# ESP32S3.net
KiCad netlist of a schematic drawn in Altium Designer
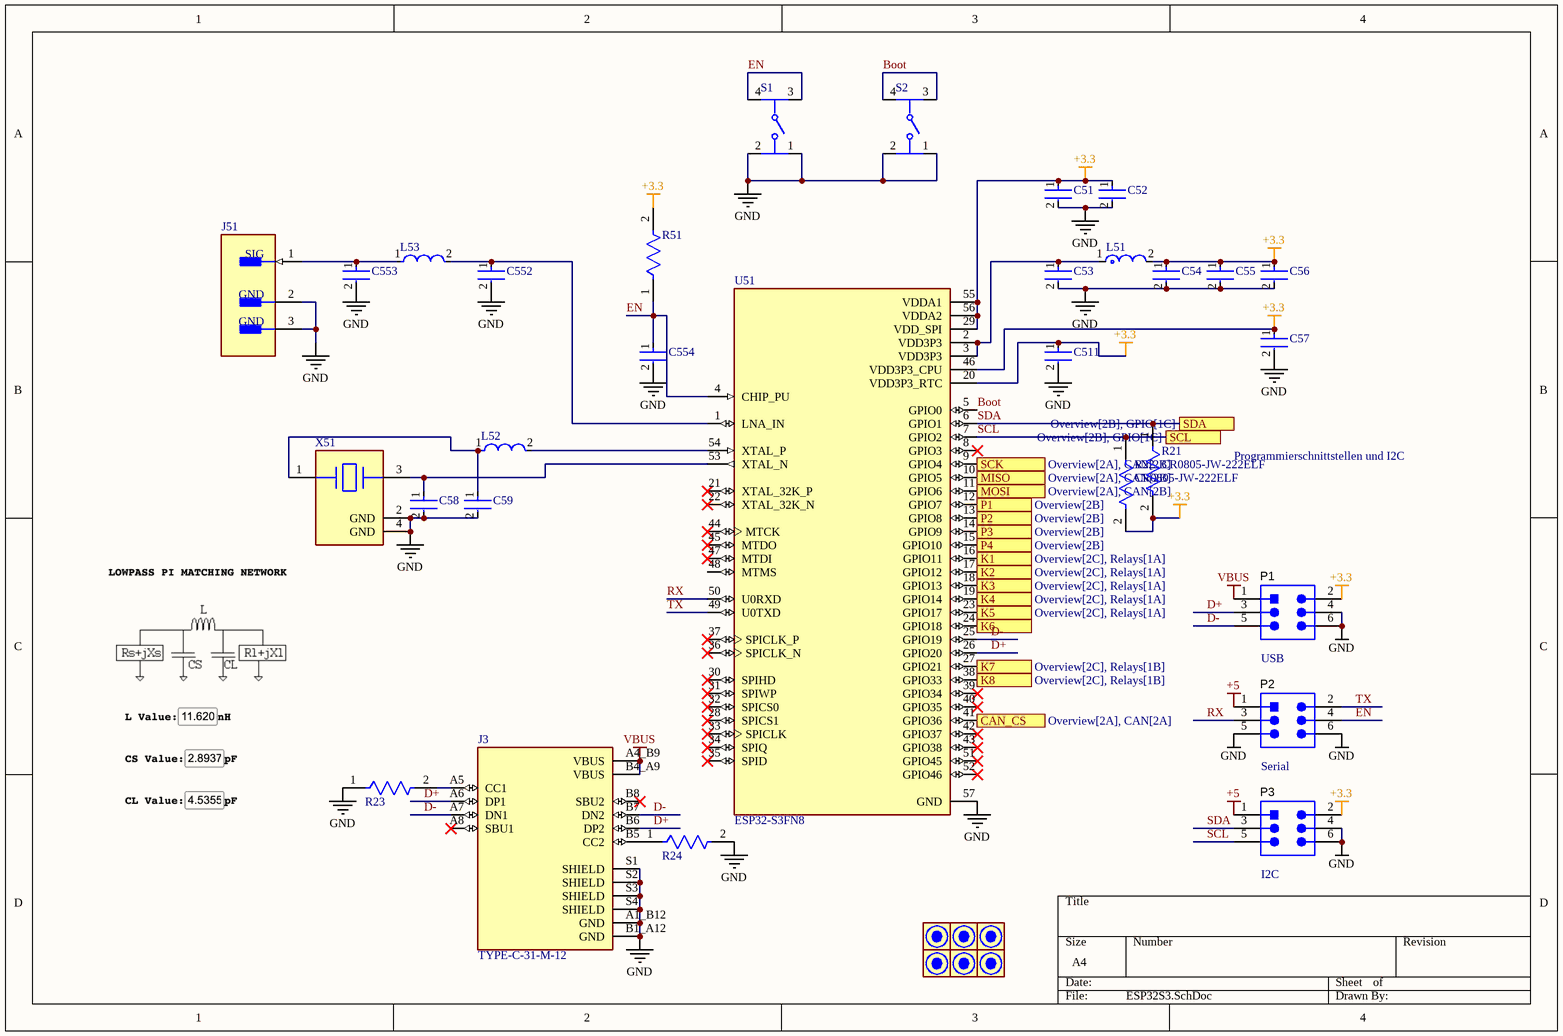
[diagram p0: ESP32S3.SchDoc]

(export (version "E")
  (design (tool "Eeschema 10.0.6"))
  (components
    (comp (ref "C51")
      (value "GRM155R61A105KE15D")
      (footprint "FP-GRM15-0_1-MFG")
      (description "CAP CER 1UF 10V X5R 0402")
      (fields
        (field (name "OCTOPART") "https://octopart.com/grm155r61a105ke15d-murata-197442")
        (field (name "MANUFACTURER") "Murata")
      )
      (libsource (lib "Altium Content Vault") (part "02cd4be3c70576c341d710602a673aa"))
    )
    (comp (ref "C52")
      (value "C0603C103K8RACTU")
      (footprint "FP-C0603C-CF-MFG")
      (description "CAP CER 10000PF 10V X7R 0603")
      (fields
        (field (name "OCTOPART") "https://octopart.com/c0603c103k8ractu-kemet-8375724")
        (field (name "MANUFACTURER") "KEMET")
      )
      (libsource (lib "Altium Content Vault") (part "b4654b650e69147ec39a6b967a45e02"))
    )
    (comp (ref "C53")
      (value "CC0402KRX7R6BB104")
      (footprint "FP-CC0402-MFG")
      (description "CAP CER 0.1UF 10V X7R 0402")
      (fields (field (name "MANUFACTURER") "YAGEO") (field (name "TOLERANCE") "0.1"))
      (libsource (lib "Altium Content Vault") (part "11868f565c42a9108669ba33697ecf6"))
    )
    (comp (ref "C54")
      (value "C0402C104K8PACTU")
      (footprint "FP-C0402-BB-MFG")
      (description "CAP CER 0.1UF 10V X5R 0402")
      (fields (field (name "MANUFACTURER") "Kemet") (field (name "TOLERANCE") "0.1"))
      (libsource (lib "Altium Content Vault") (part "b4654b650e69147ec39a6b967a45e02"))
    )
    (comp (ref "C55")
      (value "GRM155R61A105KE15D")
      (footprint "FP-GRM15-0_1-MFG")
      (description "CAP CER 1UF 10V X5R 0402")
      (fields
        (field (name "OCTOPART") "https://octopart.com/grm155r61a105ke15d-murata-197442")
        (field (name "MANUFACTURER") "Murata")
      )
      (libsource (lib "Altium Content Vault") (part "02cd4be3c70576c341d710602a673aa"))
    )
    (comp (ref "C56")
      (value "CL05A106MP5NUNC")
      (footprint "FP-CL05A106MP5NUNC-MFG")
      (description "CAP CER 10UF 10V X5R 0402")
      (fields
        (field (name "OCTOPART") "https://octopart.com/cl05a106mp5nunc-samsung-22457395")
        (field (name "TOLERANCE") "20%")
      )
      (libsource (lib "Altium Content Vault") (part "b4654b650e69147ec39a6b967a45e02"))
    )
    (comp (ref "C57")
      (value "C0402C104K8PACTU")
      (footprint "FP-C0402-BB-MFG")
      (description "CAP CER 0.1UF 10V X5R 0402")
      (fields (field (name "MANUFACTURER") "Kemet") (field (name "TOLERANCE") "0.1"))
      (libsource (lib "Altium Content Vault") (part "b4654b650e69147ec39a6b967a45e02"))
    )
    (comp (ref "C58")
      (value "C0603C160J5GACTU")
      (footprint "FP-C0603C-CF-MFG")
      (description "CAP CER 16PF 50V 5% NP0 0603")
      (fields
        (field (name "OCTOPART") "https://octopart.com/c0603c160j5gactu-kemet-9143816")
        (field (name "MANUFACTURER") "KEMET")
      )
      (libsource (lib "Altium Content Vault") (part "b4654b650e69147ec39a6b967a45e02"))
    )
    (comp (ref "C59")
      (value "C0603C160J5GACTU")
      (footprint "FP-C0603C-CF-MFG")
      (description "CAP CER 16PF 50V 5% NP0 0603")
      (fields
        (field (name "OCTOPART") "https://octopart.com/c0603c160j5gactu-kemet-9143816")
        (field (name "MANUFACTURER") "KEMET")
      )
      (libsource (lib "Altium Content Vault") (part "b4654b650e69147ec39a6b967a45e02"))
    )
    (comp (ref "C511")
      (value "CC0402KRX7R6BB104")
      (footprint "FP-CC0402-MFG")
      (description "CAP CER 0.1UF 10V X7R 0402")
      (fields (field (name "MANUFACTURER") "YAGEO") (field (name "TOLERANCE") "0.1"))
      (libsource (lib "Altium Content Vault") (part "11868f565c42a9108669ba33697ecf6"))
    )
    (comp (ref "C552")
      (value "GJM1555C1H2R8WB01D")
      (footprint "FP-GJM155-0_05-IPC_C")
      (description "Multi-Layer Ceramic Capacitor 2.8pF C0G  ±0.05pF 0402 Paper T/R")
      (libsource (lib "Altium Content Vault") (part "02cd4be3c70576c341d710602a673aa"))
    )
    (comp (ref "C553")
      (value "GJM1555C1H4R5BB01D")
      (footprint "FP-GJM155-0_05-IPC_C")
      (description "Multi-Layer Ceramic Capacitor 4.5pF C0G  ±0.1pF 0402 Paper T/R")
      (libsource (lib "Altium Content Vault") (part "02cd4be3c70576c341d710602a673aa"))
    )
    (comp (ref "C554")
      (value "C0402C123K4RACTU")
      (footprint "FP-C0402-BB-MFG")
      (description "CAP CER 0.012UF 16V X7R 0402")
      (fields (field (name "TOLERANCE") "0.1") (field (name "MANUFACTURER") "Kemet"))
      (libsource (lib "Altium Content Vault") (part "b4654b650e69147ec39a6b967a45e02"))
    )
    (comp (ref "J3")
      (value "TYPE-C-31-M-12")
      (footprint "HRO_TYPE-C-31-M-12")
      (description "USB Connectors 24 Receptacle 1 8.94*7.3mm RoHS")
      (fields (field (name "MF") "HRO Electronics Co., Ltd."))
      (libsource (lib "Milutin") (part "TYPE-C-31-M-12"))
    )
    (comp (ref "J51")
      (value "U.FL-R-SMT-1(10)")
      (footprint "FP-U_FL-R-SMT-1_10-MFG")
      (description "CONN U.FL RCPT STR 50 OHM SMD")
      (libsource (lib "Altium Content Vault") (part "7158abf7d987fa84906f6fb0d115710"))
    )
    (comp (ref "L51")
      (value "LQP03TN2N0B02D")
      (footprint "FP-LQP03TG_02-IPC_A")
      (description "Film type RF Inductor 2nH ±0.1nH 600mA 0.15Ω 0201 (0603)")
      (libsource (lib "Altium Content Vault") (part "4cc4b267dca4c8e51f7102f422741d8"))
    )
    (comp (ref "L52")
      (value "LQW15AN20NG00D")
      (footprint "FP-LQW15AN_00-W0_6-0_1-MFG")
      (description "Wire Wound RF Inductor 20nH ±2% 370mA 0.27Ω 0402 (1005)")
      (fields (field (name "TOLERANCE") "2%"))
      (libsource (lib "Altium Content Vault") (part "725321dda6339637d4d059423bc1c3c"))
    )
    (comp (ref "L53")
      (value "LQW15AN11NG00D")
      (footprint "FP-LQW15AN_00-W0_6-0_1-MFG")
      (description "Wire Wound RF Inductor 11nH ±2% 500mA 0.14Ω 0402 (1005)")
      (fields (field (name "TOLERANCE") "2%"))
      (libsource (lib "Altium Content Vault") (part "725321dda6339637d4d059423bc1c3c"))
    )
    (comp (ref "P1")
      (value "5-146130-2")
      (footprint "TECO-5-146130-2_V")
      (description "Male Header, Pitch 2.54 mm, 2 x 3 Position, Height 8.13 mm, -65 to 125 degC, RoHS, Tube")
      (libsource (lib "Altium Content Vault") (part "CN-2P-M-R6"))
    )
    (comp (ref "P2")
      (value "5-146130-2")
      (footprint "TECO-5-146130-2_V")
      (description "Male Header, Pitch 2.54 mm, 2 x 3 Position, Height 8.13 mm, -65 to 125 degC, RoHS, Tube")
      (libsource (lib "Altium Content Vault") (part "CN-2P-M-R6"))
    )
    (comp (ref "P3")
      (value "5-146130-2")
      (footprint "TECO-5-146130-2_V")
      (description "Male Header, Pitch 2.54 mm, 2 x 3 Position, Height 8.13 mm, -65 to 125 degC, RoHS, Tube")
      (libsource (lib "Altium Content Vault") (part "CN-2P-M-R6"))
    )
    (comp (ref "R21")
      (value "CR0805-JW-222ELF")
      (footprint "FP-CR0805-IPC_B")
      (description "Thick Film Chip Resistors 0805 2.2kΩ 0.125W 5% 200ppm/°C")
      (fields (field (name "TOLERANCE") "5%"))
      (libsource (lib "Altium Content Vault") (part "1029c3af85768c4190bb7ad29bc67b5"))
    )
    (comp (ref "R22")
      (value "CR0805-JW-222ELF")
      (footprint "FP-CR0805-IPC_B")
      (description "Thick Film Chip Resistors 0805 2.2kΩ 0.125W 5% 200ppm/°C")
      (fields (field (name "TOLERANCE") "5%"))
      (libsource (lib "Altium Content Vault") (part "1029c3af85768c4190bb7ad29bc67b5"))
    )
    (comp (ref "R23")
      (value "CRCW06035K10FKEA")
      (footprint "FP-CRCW0603-e3-IPC_C")
      (description "RES Thick Film, 5.1kΩ, 1%, 0.1W, 100ppm/°C, 0603")
      (fields (field (name "TOLERANCE") "1%"))
      (libsource (lib "Altium Content Vault") (part "1029c3af85768c4190bb7ad29bc67b5"))
    )
    (comp (ref "R24")
      (value "CRCW06035K10FKEA")
      (footprint "FP-CRCW0603-e3-IPC_C")
      (description "RES Thick Film, 5.1kΩ, 1%, 0.1W, 100ppm/°C, 0603")
      (fields (field (name "TOLERANCE") "1%"))
      (libsource (lib "Altium Content Vault") (part "1029c3af85768c4190bb7ad29bc67b5"))
    )
    (comp (ref "R51")
      (value "CRCW04021K00FKED")
      (footprint "FP-CRCW0402-e3-MFG")
      (description "RES Thick Film, 1kΩ, 1%, 0.063W, 100ppm/°C, 0402")
      (fields (field (name "TOLERANCE") "1%"))
      (libsource (lib "Altium Content Vault") (part "1029c3af85768c4190bb7ad29bc67b5"))
    )
    (comp (ref "S1")
      (value "~")
      (footprint "FP-PTS645SM43SMTR92LFS-MFG")
      (description "SWITCH TACTILE SPST-NO 0.05A 12V\r\nPTS645SM43SMTR92LFS")
      (libsource (lib "Altium Content Vault") (part "1adf0dd01260c80cf25a44bfd6b99ba"))
    )
    (comp (ref "S2")
      (value "~")
      (footprint "FP-PTS645SM43SMTR92LFS-MFG")
      (description "SWITCH TACTILE SPST-NO 0.05A 12V\r\nPTS645SM43SMTR92LFS")
      (libsource (lib "Altium Content Vault") (part "1adf0dd01260c80cf25a44bfd6b99ba"))
    )
    (comp (ref "U51")
      (value "ESP32-S3FN8")
      (footprint "QFN40P700X700X90-57N")
      (fields (field (name "MF") "Espressif Systems"))
      (libsource (lib "Schaltdose") (part "ESP32-S3FN8"))
    )
    (comp (ref "X51")
      (value "X252040MMB4SI")
      (footprint "FP-ABM10-MFG")
      (description "Crystal 40MHz ±20ppm 10pF SMD-4 2.5mm x 2mm")
      (fields (field (name "TOLERANCE") "20ppm"))
      (libsource (lib "Altium Content Vault") (part "0934ba461506c7e3a0bb4df7a4ed385"))
    )
  )
  (nets
    (net (code "1") (name "+3.3") (class "Default")
      (node (ref "C51") (pin "1") (pinfunction "1_1") (pintype "passive"))
      (node (ref "C511") (pin "1") (pinfunction "1_1") (pintype "passive"))
      (node (ref "C52") (pin "1") (pinfunction "1_1") (pintype "passive"))
      (node (ref "C54") (pin "1") (pinfunction "1_1") (pintype "passive"))
      (node (ref "C55") (pin "1") (pinfunction "1_1") (pintype "passive"))
      (node (ref "C56") (pin "1") (pinfunction "1_1") (pintype "passive"))
      (node (ref "C57") (pin "1") (pinfunction "1_1") (pintype "passive"))
      (node (ref "L51") (pin "2") (pinfunction "2_2") (pintype "passive"))
      (node (ref "P1") (pin "2") (pinfunction "2_2") (pintype "passive"))
      (node (ref "P3") (pin "2") (pinfunction "2_2") (pintype "passive"))
      (node (ref "R21") (pin "2") (pinfunction "2_2") (pintype "passive"))
      (node (ref "R22") (pin "2") (pinfunction "2_2") (pintype "passive"))
      (node (ref "R51") (pin "2") (pinfunction "2_2") (pintype "passive"))
      (node (ref "U51") (pin "20") (pinfunction "VDD3P3_RTC_20") (pintype "power_in"))
      (node (ref "U51") (pin "29") (pinfunction "VDD_SPI_29") (pintype "power_in"))
      (node (ref "U51") (pin "46") (pinfunction "VDD3P3_CPU_46") (pintype "power_in"))
      (node (ref "U51") (pin "55") (pinfunction "VDDA1_55") (pintype "power_in"))
      (node (ref "U51") (pin "56") (pinfunction "VDDA2_56") (pintype "power_in"))
    )
    (net (code "2") (name "+5") (class "Default")
      (node (ref "P2") (pin "1") (pinfunction "1_1") (pintype "passive"))
      (node (ref "P3") (pin "1") (pinfunction "1_1") (pintype "passive"))
    )
    (net (code "3") (name "/Boot") (class "Default")
      (node (ref "S2") (pin "3") (pinfunction "3_3") (pintype "passive"))
      (node (ref "S2") (pin "4") (pinfunction "4_4") (pintype "passive"))
      (node (ref "U51") (pin "5") (pinfunction "GPIO0_5") (pintype "bidirectional"))
    )
    (net (code "4") (name "/CAN_CS") (class "Default")
      (node (ref "U51") (pin "41") (pinfunction "GPIO36_41") (pintype "bidirectional"))
    )
    (net (code "5") (name "/D+") (class "Default")
      (node (ref "J3") (pin "A6") (pinfunction "DP1_A6") (pintype "bidirectional"))
      (node (ref "J3") (pin "B6") (pinfunction "DP2_B6") (pintype "bidirectional"))
      (node (ref "P1") (pin "3") (pinfunction "3_3") (pintype "passive"))
      (node (ref "U51") (pin "26") (pinfunction "GPIO20_26") (pintype "bidirectional"))
    )
    (net (code "6") (name "/D-") (class "Default")
      (node (ref "J3") (pin "A7") (pinfunction "DN1_A7") (pintype "bidirectional"))
      (node (ref "J3") (pin "B7") (pinfunction "DN2_B7") (pintype "bidirectional"))
      (node (ref "P1") (pin "5") (pinfunction "5_5") (pintype "passive"))
      (node (ref "U51") (pin "25") (pinfunction "GPIO19_25") (pintype "bidirectional"))
    )
    (net (code "7") (name "/EN") (class "Default")
      (node (ref "C554") (pin "1") (pinfunction "1_1") (pintype "passive"))
      (node (ref "P2") (pin "4") (pinfunction "4_4") (pintype "passive"))
      (node (ref "R51") (pin "1") (pinfunction "1_1") (pintype "passive"))
      (node (ref "S1") (pin "3") (pinfunction "3_3") (pintype "passive"))
      (node (ref "S1") (pin "4") (pinfunction "4_4") (pintype "passive"))
      (node (ref "U51") (pin "4") (pinfunction "CHIP_PU_4") (pintype "input"))
    )
    (net (code "8") (name "/K1") (class "Default")
      (node (ref "U51") (pin "16") (pinfunction "GPIO11_16") (pintype "bidirectional"))
    )
    (net (code "9") (name "/K2") (class "Default")
      (node (ref "U51") (pin "17") (pinfunction "GPIO12_17") (pintype "bidirectional"))
    )
    (net (code "10") (name "/K3") (class "Default")
      (node (ref "U51") (pin "18") (pinfunction "GPIO13_18") (pintype "bidirectional"))
    )
    (net (code "11") (name "/K4") (class "Default")
      (node (ref "U51") (pin "19") (pinfunction "GPIO14_19") (pintype "bidirectional"))
    )
    (net (code "12") (name "/K5") (class "Default")
      (node (ref "U51") (pin "23") (pinfunction "GPIO17_23") (pintype "bidirectional"))
    )
    (net (code "13") (name "/K6") (class "Default")
      (node (ref "U51") (pin "24") (pinfunction "GPIO18_24") (pintype "bidirectional"))
    )
    (net (code "14") (name "/K7") (class "Default")
      (node (ref "U51") (pin "27") (pinfunction "GPIO21_27") (pintype "bidirectional"))
    )
    (net (code "15") (name "/K8") (class "Default")
      (node (ref "U51") (pin "38") (pinfunction "GPIO33_38") (pintype "bidirectional"))
    )
    (net (code "16") (name "/MISO") (class "Default")
      (node (ref "U51") (pin "10") (pinfunction "GPIO5_10") (pintype "bidirectional"))
    )
    (net (code "17") (name "/MOSI") (class "Default")
      (node (ref "U51") (pin "11") (pinfunction "GPIO6_11") (pintype "bidirectional"))
    )
    (net (code "18") (name "/P1") (class "Default")
      (node (ref "U51") (pin "12") (pinfunction "GPIO7_12") (pintype "bidirectional"))
    )
    (net (code "19") (name "/P2") (class "Default")
      (node (ref "U51") (pin "13") (pinfunction "GPIO8_13") (pintype "bidirectional"))
    )
    (net (code "20") (name "/P3") (class "Default")
      (node (ref "U51") (pin "14") (pinfunction "GPIO9_14") (pintype "bidirectional"))
    )
    (net (code "21") (name "/P4") (class "Default")
      (node (ref "U51") (pin "15") (pinfunction "GPIO10_15") (pintype "bidirectional"))
    )
    (net (code "22") (name "/RX") (class "Default")
      (node (ref "P2") (pin "3") (pinfunction "3_3") (pintype "passive"))
      (node (ref "U51") (pin "50") (pinfunction "U0RXD_50") (pintype "bidirectional"))
    )
    (net (code "23") (name "/SCK") (class "Default")
      (node (ref "U51") (pin "9") (pinfunction "GPIO4_9") (pintype "bidirectional"))
    )
    (net (code "24") (name "/SCL") (class "Default")
      (node (ref "P3") (pin "5") (pinfunction "5_5") (pintype "passive"))
      (node (ref "R22") (pin "1") (pinfunction "1_1") (pintype "passive"))
      (node (ref "U51") (pin "7") (pinfunction "GPIO2_7") (pintype "bidirectional"))
    )
    (net (code "25") (name "/SDA") (class "Default")
      (node (ref "P3") (pin "3") (pinfunction "3_3") (pintype "passive"))
      (node (ref "R21") (pin "1") (pinfunction "1_1") (pintype "passive"))
      (node (ref "U51") (pin "6") (pinfunction "GPIO1_6") (pintype "bidirectional"))
    )
    (net (code "26") (name "/TX") (class "Default")
      (node (ref "P2") (pin "2") (pinfunction "2_2") (pintype "passive"))
      (node (ref "U51") (pin "49") (pinfunction "U0TXD_49") (pintype "bidirectional"))
    )
    (net (code "27") (name "GND") (class "Default")
      (node (ref "C51") (pin "2") (pinfunction "2_2") (pintype "passive"))
      (node (ref "C511") (pin "2") (pinfunction "2_2") (pintype "passive"))
      (node (ref "C52") (pin "2") (pinfunction "2_2") (pintype "passive"))
      (node (ref "C53") (pin "2") (pinfunction "2_2") (pintype "passive"))
      (node (ref "C54") (pin "2") (pinfunction "2_2") (pintype "passive"))
      (node (ref "C55") (pin "2") (pinfunction "2_2") (pintype "passive"))
      (node (ref "C552") (pin "2") (pinfunction "2_2") (pintype "passive"))
      (node (ref "C553") (pin "2") (pinfunction "2_2") (pintype "passive"))
      (node (ref "C554") (pin "2") (pinfunction "2_2") (pintype "passive"))
      (node (ref "C56") (pin "2") (pinfunction "2_2") (pintype "passive"))
      (node (ref "C57") (pin "2") (pinfunction "2_2") (pintype "passive"))
      (node (ref "C58") (pin "2") (pinfunction "2_2") (pintype "passive"))
      (node (ref "C59") (pin "2") (pinfunction "2_2") (pintype "passive"))
      (node (ref "J3") (pin "A1_B12") (pinfunction "GND_A1_B12") (pintype "power_in"))
      (node (ref "J3") (pin "B1_A12") (pinfunction "GND_B1_A12") (pintype "power_in"))
      (node (ref "J3") (pin "S1") (pinfunction "SHIELD_S1") (pintype "passive"))
      (node (ref "J3") (pin "S2") (pinfunction "SHIELD_S2") (pintype "passive"))
      (node (ref "J3") (pin "S3") (pinfunction "SHIELD_S3") (pintype "passive"))
      (node (ref "J3") (pin "S4") (pinfunction "SHIELD_S4") (pintype "passive"))
      (node (ref "J51") (pin "2") (pinfunction "GND_2") (pintype "power_in"))
      (node (ref "J51") (pin "3") (pinfunction "GND_3") (pintype "power_in"))
      (node (ref "P1") (pin "4") (pinfunction "4_4") (pintype "passive"))
      (node (ref "P1") (pin "6") (pinfunction "6_6") (pintype "passive"))
      (node (ref "P2") (pin "5") (pinfunction "5_5") (pintype "passive"))
      (node (ref "P2") (pin "6") (pinfunction "6_6") (pintype "passive"))
      (node (ref "P3") (pin "4") (pinfunction "4_4") (pintype "passive"))
      (node (ref "P3") (pin "6") (pinfunction "6_6") (pintype "passive"))
      (node (ref "R23") (pin "1") (pinfunction "1_1") (pintype "passive"))
      (node (ref "R24") (pin "2") (pinfunction "2_2") (pintype "passive"))
      (node (ref "S1") (pin "1") (pinfunction "1_1") (pintype "passive"))
      (node (ref "S1") (pin "2") (pinfunction "2_2") (pintype "passive"))
      (node (ref "S2") (pin "1") (pinfunction "1_1") (pintype "passive"))
      (node (ref "S2") (pin "2") (pinfunction "2_2") (pintype "passive"))
      (node (ref "U51") (pin "57") (pinfunction "GND_57") (pintype "power_in"))
      (node (ref "X51") (pin "2") (pinfunction "GND_2") (pintype "power_in"))
      (node (ref "X51") (pin "4") (pinfunction "GND_4") (pintype "power_in"))
    )
    (net (code "28") (name "Net-(C53-Pad1)") (class "Default")
      (node (ref "C53") (pin "1") (pinfunction "1_1") (pintype "passive"))
      (node (ref "L51") (pin "1") (pinfunction "1_1") (pintype "passive"))
      (node (ref "U51") (pin "2") (pinfunction "VDD3P3_2") (pintype "power_in"))
      (node (ref "U51") (pin "3") (pinfunction "VDD3P3_3") (pintype "power_in"))
    )
    (net (code "29") (name "Net-(C59-Pad1)") (class "Default")
      (node (ref "C59") (pin "1") (pinfunction "1_1") (pintype "passive"))
      (node (ref "L52") (pin "1") (pinfunction "1_1") (pintype "passive"))
      (node (ref "X51") (pin "1") (pinfunction "1_1") (pintype "passive"))
    )
    (net (code "30") (name "Net-(J3-CC1)") (class "Default")
      (node (ref "J3") (pin "A5") (pinfunction "CC1_A5") (pintype "bidirectional"))
      (node (ref "R23") (pin "2") (pinfunction "2_2") (pintype "passive"))
    )
    (net (code "31") (name "Net-(J3-CC2)") (class "Default")
      (node (ref "J3") (pin "B5") (pinfunction "CC2_B5") (pintype "bidirectional"))
      (node (ref "R24") (pin "1") (pinfunction "1_1") (pintype "passive"))
    )
    (net (code "32") (name "Net-(J51-SIG)") (class "Default")
      (node (ref "C553") (pin "1") (pinfunction "1_1") (pintype "passive"))
      (node (ref "J51") (pin "1") (pinfunction "SIG_1") (pintype "input"))
      (node (ref "L53") (pin "1") (pinfunction "1_1") (pintype "passive"))
    )
    (net (code "33") (name "Net-(U51-LNA_IN)") (class "Default")
      (node (ref "C552") (pin "1") (pinfunction "1_1") (pintype "passive"))
      (node (ref "L53") (pin "2") (pinfunction "2_2") (pintype "passive"))
      (node (ref "U51") (pin "1") (pinfunction "LNA_IN_1") (pintype "bidirectional"))
    )
    (net (code "34") (name "Net-(U51-XTAL_N)") (class "Default")
      (node (ref "C58") (pin "1") (pinfunction "1_1") (pintype "passive"))
      (node (ref "U51") (pin "53") (pinfunction "XTAL_N_53") (pintype "output"))
      (node (ref "X51") (pin "3") (pinfunction "3_3") (pintype "passive"))
    )
    (net (code "35") (name "Net-(U51-XTAL_P)") (class "Default")
      (node (ref "L52") (pin "2") (pinfunction "2_2") (pintype "passive"))
      (node (ref "U51") (pin "54") (pinfunction "XTAL_P_54") (pintype "input"))
    )
    (net (code "36") (name "VBUS") (class "Default")
      (node (ref "J3") (pin "A4_B9") (pinfunction "VBUS_A4_B9") (pintype "power_in"))
      (node (ref "J3") (pin "B4_A9") (pinfunction "VBUS_B4_A9") (pintype "power_in"))
      (node (ref "P1") (pin "1") (pinfunction "1_1") (pintype "passive"))
    )
    (net (code "37") (name "unconnected-(J3-SBU1-PadA8)") (class "Default")
      (node (ref "J3") (pin "A8") (pinfunction "SBU1_A8") (pintype "bidirectional+no_connect"))
    )
    (net (code "38") (name "unconnected-(J3-SBU2-PadB8)") (class "Default")
      (node (ref "J3") (pin "B8") (pinfunction "SBU2_B8") (pintype "bidirectional+no_connect"))
    )
    (net (code "39") (name "unconnected-(U51-GPIO3-Pad8)") (class "Default")
      (node (ref "U51") (pin "8") (pinfunction "GPIO3_8") (pintype "bidirectional+no_connect"))
    )
    (net (code "40") (name "unconnected-(U51-GPIO34-Pad39)") (class "Default")
      (node (ref "U51") (pin "39") (pinfunction "GPIO34_39") (pintype "bidirectional+no_connect"))
    )
    (net (code "41") (name "unconnected-(U51-GPIO35-Pad40)") (class "Default")
      (node (ref "U51") (pin "40") (pinfunction "GPIO35_40") (pintype "bidirectional+no_connect"))
    )
    (net (code "42") (name "unconnected-(U51-GPIO37-Pad42)") (class "Default")
      (node (ref "U51") (pin "42") (pinfunction "GPIO37_42") (pintype "bidirectional+no_connect"))
    )
    (net (code "43") (name "unconnected-(U51-GPIO38-Pad43)") (class "Default")
      (node (ref "U51") (pin "43") (pinfunction "GPIO38_43") (pintype "bidirectional+no_connect"))
    )
    (net (code "44") (name "unconnected-(U51-GPIO45-Pad51)") (class "Default")
      (node (ref "U51") (pin "51") (pinfunction "GPIO45_51") (pintype "bidirectional+no_connect"))
    )
    (net (code "45") (name "unconnected-(U51-GPIO46-Pad52)") (class "Default")
      (node (ref "U51") (pin "52") (pinfunction "GPIO46_52") (pintype "bidirectional+no_connect"))
    )
    (net (code "46") (name "unconnected-(U51-MTCK-Pad44)") (class "Default")
      (node (ref "U51") (pin "44") (pinfunction "MTCK_44") (pintype "bidirectional+no_connect"))
    )
    (net (code "47") (name "unconnected-(U51-MTDI-Pad47)") (class "Default")
      (node (ref "U51") (pin "47") (pinfunction "MTDI_47") (pintype "bidirectional+no_connect"))
    )
    (net (code "48") (name "unconnected-(U51-MTDO-Pad45)") (class "Default")
      (node (ref "U51") (pin "45") (pinfunction "MTDO_45") (pintype "bidirectional+no_connect"))
    )
    (net (code "49") (name "unconnected-(U51-MTMS-Pad48)") (class "Default")
      (node (ref "U51") (pin "48") (pinfunction "MTMS_48") (pintype "bidirectional"))
    )
    (net (code "50") (name "unconnected-(U51-SPICLK-Pad33)") (class "Default")
      (node (ref "U51") (pin "33") (pinfunction "SPICLK_33") (pintype "bidirectional+no_connect"))
    )
    (net (code "51") (name "unconnected-(U51-SPICLK_N-Pad36)") (class "Default")
      (node (ref "U51") (pin "36") (pinfunction "SPICLK_N_36") (pintype "bidirectional+no_connect"))
    )
    (net (code "52") (name "unconnected-(U51-SPICLK_P-Pad37)") (class "Default")
      (node (ref "U51") (pin "37") (pinfunction "SPICLK_P_37") (pintype "bidirectional+no_connect"))
    )
    (net (code "53") (name "unconnected-(U51-SPICS0-Pad32)") (class "Default")
      (node (ref "U51") (pin "32") (pinfunction "SPICS0_32") (pintype "bidirectional+no_connect"))
    )
    (net (code "54") (name "unconnected-(U51-SPICS1-Pad28)") (class "Default")
      (node (ref "U51") (pin "28") (pinfunction "SPICS1_28") (pintype "bidirectional+no_connect"))
    )
    (net (code "55") (name "unconnected-(U51-SPID-Pad35)") (class "Default")
      (node (ref "U51") (pin "35") (pinfunction "SPID_35") (pintype "bidirectional+no_connect"))
    )
    (net (code "56") (name "unconnected-(U51-SPIHD-Pad30)") (class "Default")
      (node (ref "U51") (pin "30") (pinfunction "SPIHD_30") (pintype "bidirectional+no_connect"))
    )
    (net (code "57") (name "unconnected-(U51-SPIQ-Pad34)") (class "Default")
      (node (ref "U51") (pin "34") (pinfunction "SPIQ_34") (pintype "bidirectional+no_connect"))
    )
    (net (code "58") (name "unconnected-(U51-SPIWP-Pad31)") (class "Default")
      (node (ref "U51") (pin "31") (pinfunction "SPIWP_31") (pintype "bidirectional+no_connect"))
    )
    (net (code "59") (name "unconnected-(U51-XTAL_32K_N-Pad22)") (class "Default")
      (node (ref "U51") (pin "22") (pinfunction "XTAL_32K_N_22") (pintype "bidirectional+no_connect"))
    )
    (net (code "60") (name "unconnected-(U51-XTAL_32K_P-Pad21)") (class "Default")
      (node (ref "U51") (pin "21") (pinfunction "XTAL_32K_P_21") (pintype "bidirectional+no_connect"))
    )
  )
)
